# ramp-timebase.net
KiCad netlist of a schematic drawn in EAGLE
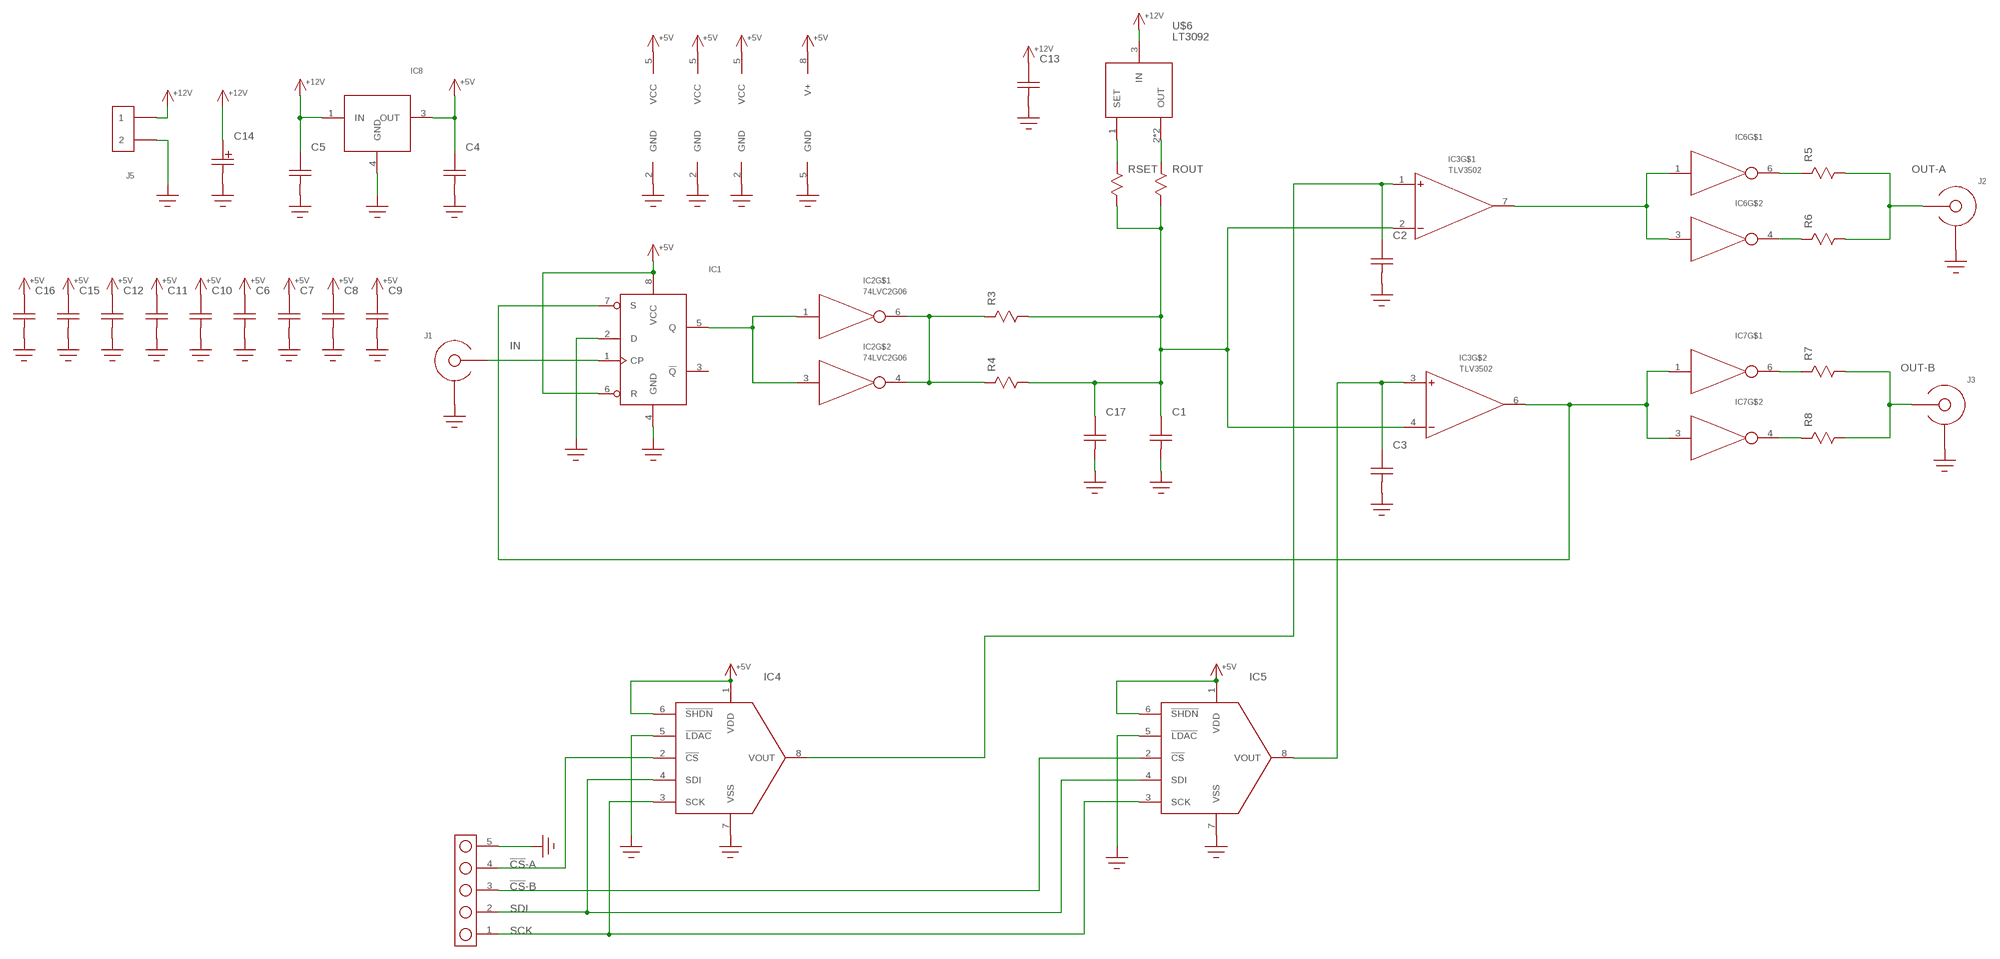
[diagram p0: schematic, sheet 1]

(export (version "E")
  (design (tool "Eeschema 10.0.6"))
  (components
    (comp (ref "C1")
      (value "C0603")
      (footprint "eagle-import:C0603")
      (libsource (lib "eagle-import") (part "C0603"))
    )
    (comp (ref "C2")
      (value "C0603")
      (footprint "eagle-import:C0603")
      (libsource (lib "eagle-import") (part "C0603"))
    )
    (comp (ref "C3")
      (value "C0603")
      (footprint "eagle-import:C0603")
      (libsource (lib "eagle-import") (part "C0603"))
    )
    (comp (ref "C4")
      (value "C1206")
      (footprint "eagle-import:1206")
      (libsource (lib "eagle-import") (part "C1206"))
    )
    (comp (ref "C5")
      (value "C1206")
      (footprint "eagle-import:1206")
      (libsource (lib "eagle-import") (part "C1206"))
    )
    (comp (ref "C6")
      (value "C0603")
      (footprint "eagle-import:C0603")
      (libsource (lib "eagle-import") (part "C0603"))
    )
    (comp (ref "C7")
      (value "C0603")
      (footprint "eagle-import:C0603")
      (libsource (lib "eagle-import") (part "C0603"))
    )
    (comp (ref "C8")
      (value "C0603")
      (footprint "eagle-import:C0603")
      (libsource (lib "eagle-import") (part "C0603"))
    )
    (comp (ref "C9")
      (value "C0603")
      (footprint "eagle-import:C0603")
      (libsource (lib "eagle-import") (part "C0603"))
    )
    (comp (ref "C10")
      (value "C0603")
      (footprint "eagle-import:C0603")
      (libsource (lib "eagle-import") (part "C0603"))
    )
    (comp (ref "C11")
      (value "C0603")
      (footprint "eagle-import:C0603")
      (libsource (lib "eagle-import") (part "C0603"))
    )
    (comp (ref "C12")
      (value "C0603")
      (footprint "eagle-import:C0603")
      (libsource (lib "eagle-import") (part "C0603"))
    )
    (comp (ref "C13")
      (value "C0603")
      (footprint "eagle-import:C0603")
      (libsource (lib "eagle-import") (part "C0603"))
    )
    (comp (ref "C14")
      (value "C-POLARIZED")
      (footprint "eagle-import:CAP-E61")
      (libsource (lib "eagle-import") (part "C-POLARIZED"))
    )
    (comp (ref "C15")
      (value "C0603")
      (footprint "eagle-import:C0603")
      (libsource (lib "eagle-import") (part "C0603"))
    )
    (comp (ref "C16")
      (value "C0603")
      (footprint "eagle-import:C0603")
      (libsource (lib "eagle-import") (part "C0603"))
    )
    (comp (ref "C17")
      (value "C1206")
      (footprint "eagle-import:1206")
      (libsource (lib "eagle-import") (part "C1206"))
    )
    (comp (ref "IC1")
      (value "74LVC2G74")
      (footprint "eagle-import:SSOP8")
      (libsource (lib "eagle-import") (part "74LVC2G74"))
    )
    (comp (ref "IC2")
      (value "74LVC2G06")
      (footprint "eagle-import:SOT23-6")
      (libsource (lib "eagle-import") (part "74LVC2G04"))
    )
    (comp (ref "IC3")
      (value "TLV3502")
      (footprint "eagle-import:SOIC8")
      (libsource (lib "eagle-import") (part "TLV3502"))
    )
    (comp (ref "IC4")
      (value "MCP48X1")
      (footprint "eagle-import:SOIC8")
      (libsource (lib "eagle-import") (part "MCP48X1"))
    )
    (comp (ref "IC5")
      (value "MCP48X1")
      (footprint "eagle-import:SOIC8")
      (libsource (lib "eagle-import") (part "MCP48X1"))
    )
    (comp (ref "IC6")
      (value "74LVC2G04")
      (footprint "eagle-import:SOT23-6")
      (libsource (lib "eagle-import") (part "74LVC2G04"))
    )
    (comp (ref "IC7")
      (value "74LVC2G04")
      (footprint "eagle-import:SOT23-6")
      (libsource (lib "eagle-import") (part "74LVC2G04"))
    )
    (comp (ref "IC8")
      (value "MC78M00")
      (footprint "eagle-import:DPAK")
      (libsource (lib "eagle-import") (part "MC78M00"))
    )
    (comp (ref "J1")
      (value "SMA-EDGE-LAUNCH4020_TAPER")
      (footprint "eagle-import:SMA_EDGE_LAUNCH_2L_4020_TAPER")
      (libsource (lib "eagle-import") (part "SMA-EDGE-LAUNCH4020_TAPER"))
    )
    (comp (ref "J2")
      (value "SMA-EDGE-LAUNCH4020_TAPER")
      (footprint "eagle-import:SMA_EDGE_LAUNCH_2L_4020_TAPER")
      (libsource (lib "eagle-import") (part "SMA-EDGE-LAUNCH4020_TAPER"))
    )
    (comp (ref "J3")
      (value "SMA-EDGE-LAUNCH4020_TAPER")
      (footprint "eagle-import:SMA_EDGE_LAUNCH_2L_4020_TAPER")
      (libsource (lib "eagle-import") (part "SMA-EDGE-LAUNCH4020_TAPER"))
    )
    (comp (ref "J4")
      (value "HEADER_5PIN")
      (footprint "eagle-import:HEADER_5PIN")
      (libsource (lib "eagle-import") (part "HEADER_5PIN"))
    )
    (comp (ref "J5")
      (value "HEADER_2PINSCREW-TERM")
      (footprint "eagle-import:FCI_20020316_SCREW_TERM_2P")
      (libsource (lib "eagle-import") (part "HEADER_2PINSCREW-TERM"))
    )
    (comp (ref "R3")
      (value "R0805")
      (footprint "eagle-import:R0805")
      (libsource (lib "eagle-import") (part "R0805"))
    )
    (comp (ref "R4")
      (value "R0805")
      (footprint "eagle-import:R0805")
      (libsource (lib "eagle-import") (part "R0805"))
    )
    (comp (ref "R5")
      (value "R1206")
      (footprint "eagle-import:R1206")
      (libsource (lib "eagle-import") (part "R1206"))
    )
    (comp (ref "R6")
      (value "R1206")
      (footprint "eagle-import:R1206")
      (libsource (lib "eagle-import") (part "R1206"))
    )
    (comp (ref "R7")
      (value "R1206")
      (footprint "eagle-import:R1206")
      (libsource (lib "eagle-import") (part "R1206"))
    )
    (comp (ref "R8")
      (value "R1206")
      (footprint "eagle-import:R1206")
      (libsource (lib "eagle-import") (part "R1206"))
    )
    (comp (ref "ROUT")
      (value "R0805")
      (footprint "eagle-import:R0805")
      (libsource (lib "eagle-import") (part "R0805"))
    )
    (comp (ref "RSET")
      (value "R0805")
      (footprint "eagle-import:R0805")
      (libsource (lib "eagle-import") (part "R0805"))
    )
    (comp (ref "U$6")
      (value "LT3092")
      (footprint "eagle-import:SOT-223")
      (libsource (lib "eagle-import") (part "LT3092"))
    )
  )
  (nets
    (net (code "1") (name "+5V") (class "Default")
      (node (ref "C10") (pin "P$2") (pinfunction "P$2_P$2") (pintype "bidirectional"))
      (node (ref "C11") (pin "P$2") (pinfunction "P$2_P$2") (pintype "bidirectional"))
      (node (ref "C12") (pin "P$2") (pinfunction "P$2_P$2") (pintype "bidirectional"))
      (node (ref "C15") (pin "P$2") (pinfunction "P$2_P$2") (pintype "bidirectional"))
      (node (ref "C16") (pin "P$2") (pinfunction "P$2_P$2") (pintype "bidirectional"))
      (node (ref "C4") (pin "P$2") (pinfunction "P$2_P$2") (pintype "bidirectional"))
      (node (ref "C6") (pin "P$2") (pinfunction "P$2_P$2") (pintype "bidirectional"))
      (node (ref "C7") (pin "P$2") (pinfunction "P$2_P$2") (pintype "bidirectional"))
      (node (ref "C8") (pin "P$2") (pinfunction "P$2_P$2") (pintype "bidirectional"))
      (node (ref "C9") (pin "P$2") (pinfunction "P$2_P$2") (pintype "bidirectional"))
      (node (ref "IC1") (pin "6") (pinfunction "R_6") (pintype "bidirectional"))
      (node (ref "IC1") (pin "8") (pinfunction "VCC_8") (pintype "bidirectional"))
      (node (ref "IC2") (pin "5") (pinfunction "VCC_5") (pintype "bidirectional"))
      (node (ref "IC3") (pin "8") (pinfunction "V+_8") (pintype "bidirectional"))
      (node (ref "IC4") (pin "1") (pinfunction "VDD_1") (pintype "bidirectional"))
      (node (ref "IC4") (pin "6") (pinfunction "~{SHDN}_6") (pintype "bidirectional"))
      (node (ref "IC5") (pin "1") (pinfunction "VDD_1") (pintype "bidirectional"))
      (node (ref "IC5") (pin "6") (pinfunction "~{SHDN}_6") (pintype "bidirectional"))
      (node (ref "IC6") (pin "5") (pinfunction "VCC_5") (pintype "bidirectional"))
      (node (ref "IC7") (pin "5") (pinfunction "VCC_5") (pintype "bidirectional"))
      (node (ref "IC8") (pin "3") (pinfunction "OUT_3") (pintype "bidirectional"))
    )
    (net (code "2") (name "+12V") (class "Default")
      (node (ref "C13") (pin "P$2") (pinfunction "P$2_P$2") (pintype "bidirectional"))
      (node (ref "C14") (pin "+") (pinfunction "+_+") (pintype "bidirectional"))
      (node (ref "C5") (pin "P$2") (pinfunction "P$2_P$2") (pintype "bidirectional"))
      (node (ref "IC8") (pin "1") (pinfunction "IN_1") (pintype "bidirectional"))
      (node (ref "J5") (pin "P$1") (pinfunction "1_P$1") (pintype "bidirectional"))
      (node (ref "U$6") (pin "3") (pinfunction "IN_3") (pintype "bidirectional"))
    )
    (net (code "3") (name "/IN") (class "Default")
      (node (ref "IC1") (pin "1") (pinfunction "CP_1") (pintype "bidirectional"))
      (node (ref "J1") (pin "CENTER@1") (pinfunction "CENTER_CENTER@1") (pintype "bidirectional"))
    )
    (net (code "4") (name "/OUT-A") (class "Default")
      (node (ref "J2") (pin "CENTER@1") (pinfunction "CENTER_CENTER@1") (pintype "bidirectional"))
      (node (ref "R5") (pin "P$2") (pinfunction "P$4_P$2") (pintype "bidirectional"))
      (node (ref "R6") (pin "P$2") (pinfunction "P$4_P$2") (pintype "bidirectional"))
    )
    (net (code "5") (name "/OUT-B") (class "Default")
      (node (ref "J3") (pin "CENTER@1") (pinfunction "CENTER_CENTER@1") (pintype "bidirectional"))
      (node (ref "R7") (pin "P$2") (pinfunction "P$4_P$2") (pintype "bidirectional"))
      (node (ref "R8") (pin "P$2") (pinfunction "P$4_P$2") (pintype "bidirectional"))
    )
    (net (code "6") (name "/SCK") (class "Default")
      (node (ref "IC4") (pin "3") (pinfunction "SCK_3") (pintype "bidirectional"))
      (node (ref "IC5") (pin "3") (pinfunction "SCK_3") (pintype "bidirectional"))
      (node (ref "J4") (pin "1") (pinfunction "1_1") (pintype "bidirectional"))
    )
    (net (code "7") (name "/SDI") (class "Default")
      (node (ref "IC4") (pin "4") (pinfunction "SDI_4") (pintype "bidirectional"))
      (node (ref "IC5") (pin "4") (pinfunction "SDI_4") (pintype "bidirectional"))
      (node (ref "J4") (pin "2") (pinfunction "2_2") (pintype "bidirectional"))
    )
    (net (code "8") (name "/~{CS}-A") (class "Default")
      (node (ref "IC4") (pin "2") (pinfunction "~{CS}_2") (pintype "bidirectional"))
      (node (ref "J4") (pin "4") (pinfunction "4_4") (pintype "bidirectional"))
    )
    (net (code "9") (name "/~{CS}-B") (class "Default")
      (node (ref "IC5") (pin "2") (pinfunction "~{CS}_2") (pintype "bidirectional"))
      (node (ref "J4") (pin "3") (pinfunction "3_3") (pintype "bidirectional"))
    )
    (net (code "10") (name "GND") (class "Default")
      (node (ref "C1") (pin "P$1") (pinfunction "P$1_P$1") (pintype "bidirectional"))
      (node (ref "C10") (pin "P$1") (pinfunction "P$1_P$1") (pintype "bidirectional"))
      (node (ref "C11") (pin "P$1") (pinfunction "P$1_P$1") (pintype "bidirectional"))
      (node (ref "C12") (pin "P$1") (pinfunction "P$1_P$1") (pintype "bidirectional"))
      (node (ref "C13") (pin "P$1") (pinfunction "P$1_P$1") (pintype "bidirectional"))
      (node (ref "C14") (pin "-") (pinfunction "-_-") (pintype "bidirectional"))
      (node (ref "C15") (pin "P$1") (pinfunction "P$1_P$1") (pintype "bidirectional"))
      (node (ref "C16") (pin "P$1") (pinfunction "P$1_P$1") (pintype "bidirectional"))
      (node (ref "C17") (pin "P$1") (pinfunction "P$1_P$1") (pintype "bidirectional"))
      (node (ref "C2") (pin "P$1") (pinfunction "P$1_P$1") (pintype "bidirectional"))
      (node (ref "C3") (pin "P$1") (pinfunction "P$1_P$1") (pintype "bidirectional"))
      (node (ref "C4") (pin "P$1") (pinfunction "P$1_P$1") (pintype "bidirectional"))
      (node (ref "C5") (pin "P$1") (pinfunction "P$1_P$1") (pintype "bidirectional"))
      (node (ref "C6") (pin "P$1") (pinfunction "P$1_P$1") (pintype "bidirectional"))
      (node (ref "C7") (pin "P$1") (pinfunction "P$1_P$1") (pintype "bidirectional"))
      (node (ref "C8") (pin "P$1") (pinfunction "P$1_P$1") (pintype "bidirectional"))
      (node (ref "C9") (pin "P$1") (pinfunction "P$1_P$1") (pintype "bidirectional"))
      (node (ref "IC1") (pin "2") (pinfunction "D_2") (pintype "bidirectional"))
      (node (ref "IC1") (pin "4") (pinfunction "GND_4") (pintype "bidirectional"))
      (node (ref "IC2") (pin "2") (pinfunction "GND_2") (pintype "bidirectional"))
      (node (ref "IC3") (pin "5") (pinfunction "GND_5") (pintype "bidirectional"))
      (node (ref "IC4") (pin "5") (pinfunction "~{LDAC}_5") (pintype "bidirectional"))
      (node (ref "IC4") (pin "7") (pinfunction "VSS_7") (pintype "bidirectional"))
      (node (ref "IC5") (pin "5") (pinfunction "~{LDAC}_5") (pintype "bidirectional"))
      (node (ref "IC5") (pin "7") (pinfunction "VSS_7") (pintype "bidirectional"))
      (node (ref "IC6") (pin "2") (pinfunction "GND_2") (pintype "bidirectional"))
      (node (ref "IC7") (pin "2") (pinfunction "GND_2") (pintype "bidirectional"))
      (node (ref "IC8") (pin "4") (pinfunction "GND_4") (pintype "bidirectional"))
      (node (ref "J1") (pin "BOTTOM_GND") (pinfunction "SHIELD_BOTTOM_GND") (pintype "bidirectional"))
      (node (ref "J1") (pin "GND@1") (pinfunction "SHIELD_GND@1") (pintype "bidirectional"))
      (node (ref "J1") (pin "GND@14") (pinfunction "SHIELD_GND@14") (pintype "bidirectional"))
      (node (ref "J1") (pin "GND@15") (pinfunction "SHIELD_GND@15") (pintype "bidirectional"))
      (node (ref "J1") (pin "GND@16") (pinfunction "SHIELD_GND@16") (pintype "bidirectional"))
      (node (ref "J1") (pin "GND@17") (pinfunction "SHIELD_GND@17") (pintype "bidirectional"))
      (node (ref "J1") (pin "GND@2") (pinfunction "SHIELD_GND@2") (pintype "bidirectional"))
      (node (ref "J1") (pin "GND@3") (pinfunction "SHIELD_GND@3") (pintype "bidirectional"))
      (node (ref "J1") (pin "GND@4") (pinfunction "SHIELD_GND@4") (pintype "bidirectional"))
      (node (ref "J1") (pin "GND@5") (pinfunction "SHIELD_GND@5") (pintype "bidirectional"))
      (node (ref "J1") (pin "GND@6") (pinfunction "SHIELD_GND@6") (pintype "bidirectional"))
      (node (ref "J1") (pin "GND@7") (pinfunction "SHIELD_GND@7") (pintype "bidirectional"))
      (node (ref "J1") (pin "GND@8") (pinfunction "SHIELD_GND@8") (pintype "bidirectional"))
      (node (ref "J1") (pin "GND_PAD1") (pinfunction "SHIELD_GND_PAD1") (pintype "bidirectional"))
      (node (ref "J1") (pin "GND_PAD2") (pinfunction "SHIELD_GND_PAD2") (pintype "bidirectional"))
      (node (ref "J1") (pin "P$1") (pinfunction "SHIELD_P$1") (pintype "bidirectional"))
      (node (ref "J1") (pin "P$2") (pinfunction "SHIELD_P$2") (pintype "bidirectional"))
      (node (ref "J2") (pin "BOTTOM_GND") (pinfunction "SHIELD_BOTTOM_GND") (pintype "bidirectional"))
      (node (ref "J2") (pin "GND@1") (pinfunction "SHIELD_GND@1") (pintype "bidirectional"))
      (node (ref "J2") (pin "GND@14") (pinfunction "SHIELD_GND@14") (pintype "bidirectional"))
      (node (ref "J2") (pin "GND@15") (pinfunction "SHIELD_GND@15") (pintype "bidirectional"))
      (node (ref "J2") (pin "GND@16") (pinfunction "SHIELD_GND@16") (pintype "bidirectional"))
      (node (ref "J2") (pin "GND@17") (pinfunction "SHIELD_GND@17") (pintype "bidirectional"))
      (node (ref "J2") (pin "GND@2") (pinfunction "SHIELD_GND@2") (pintype "bidirectional"))
      (node (ref "J2") (pin "GND@3") (pinfunction "SHIELD_GND@3") (pintype "bidirectional"))
      (node (ref "J2") (pin "GND@4") (pinfunction "SHIELD_GND@4") (pintype "bidirectional"))
      (node (ref "J2") (pin "GND@5") (pinfunction "SHIELD_GND@5") (pintype "bidirectional"))
      (node (ref "J2") (pin "GND@6") (pinfunction "SHIELD_GND@6") (pintype "bidirectional"))
      (node (ref "J2") (pin "GND@7") (pinfunction "SHIELD_GND@7") (pintype "bidirectional"))
      (node (ref "J2") (pin "GND@8") (pinfunction "SHIELD_GND@8") (pintype "bidirectional"))
      (node (ref "J2") (pin "GND_PAD1") (pinfunction "SHIELD_GND_PAD1") (pintype "bidirectional"))
      (node (ref "J2") (pin "GND_PAD2") (pinfunction "SHIELD_GND_PAD2") (pintype "bidirectional"))
      (node (ref "J2") (pin "P$1") (pinfunction "SHIELD_P$1") (pintype "bidirectional"))
      (node (ref "J2") (pin "P$2") (pinfunction "SHIELD_P$2") (pintype "bidirectional"))
      (node (ref "J3") (pin "BOTTOM_GND") (pinfunction "SHIELD_BOTTOM_GND") (pintype "bidirectional"))
      (node (ref "J3") (pin "GND@1") (pinfunction "SHIELD_GND@1") (pintype "bidirectional"))
      (node (ref "J3") (pin "GND@14") (pinfunction "SHIELD_GND@14") (pintype "bidirectional"))
      (node (ref "J3") (pin "GND@15") (pinfunction "SHIELD_GND@15") (pintype "bidirectional"))
      (node (ref "J3") (pin "GND@16") (pinfunction "SHIELD_GND@16") (pintype "bidirectional"))
      (node (ref "J3") (pin "GND@17") (pinfunction "SHIELD_GND@17") (pintype "bidirectional"))
      (node (ref "J3") (pin "GND@2") (pinfunction "SHIELD_GND@2") (pintype "bidirectional"))
      (node (ref "J3") (pin "GND@3") (pinfunction "SHIELD_GND@3") (pintype "bidirectional"))
      (node (ref "J3") (pin "GND@4") (pinfunction "SHIELD_GND@4") (pintype "bidirectional"))
      (node (ref "J3") (pin "GND@5") (pinfunction "SHIELD_GND@5") (pintype "bidirectional"))
      (node (ref "J3") (pin "GND@6") (pinfunction "SHIELD_GND@6") (pintype "bidirectional"))
      (node (ref "J3") (pin "GND@7") (pinfunction "SHIELD_GND@7") (pintype "bidirectional"))
      (node (ref "J3") (pin "GND@8") (pinfunction "SHIELD_GND@8") (pintype "bidirectional"))
      (node (ref "J3") (pin "GND_PAD1") (pinfunction "SHIELD_GND_PAD1") (pintype "bidirectional"))
      (node (ref "J3") (pin "GND_PAD2") (pinfunction "SHIELD_GND_PAD2") (pintype "bidirectional"))
      (node (ref "J3") (pin "P$1") (pinfunction "SHIELD_P$1") (pintype "bidirectional"))
      (node (ref "J3") (pin "P$2") (pinfunction "SHIELD_P$2") (pintype "bidirectional"))
      (node (ref "J4") (pin "5") (pinfunction "5_5") (pintype "bidirectional"))
      (node (ref "J5") (pin "P$2") (pinfunction "2_P$2") (pintype "bidirectional"))
    )
    (net (code "11") (name "Net-(IC1-Q)") (class "Default")
      (node (ref "IC1") (pin "5") (pinfunction "Q_5") (pintype "bidirectional"))
      (node (ref "IC2") (pin "1") (pinfunction "IN_1") (pintype "bidirectional"))
      (node (ref "IC2") (pin "3") (pinfunction "IN_3") (pintype "bidirectional"))
    )
    (net (code "12") (name "Net-(IC1-S)") (class "Default")
      (node (ref "IC1") (pin "7") (pinfunction "S_7") (pintype "bidirectional"))
      (node (ref "IC3") (pin "6") (pinfunction "OUT_6") (pintype "bidirectional"))
      (node (ref "IC7") (pin "1") (pinfunction "IN_1") (pintype "bidirectional"))
      (node (ref "IC7") (pin "3") (pinfunction "IN_3") (pintype "bidirectional"))
    )
    (net (code "13") (name "Net-(IC2A-OUT)") (class "Default")
      (node (ref "IC2") (pin "4") (pinfunction "OUT_4") (pintype "bidirectional"))
      (node (ref "IC2") (pin "6") (pinfunction "OUT_6") (pintype "bidirectional"))
      (node (ref "R3") (pin "P$1") (pinfunction "P$3_P$1") (pintype "bidirectional"))
      (node (ref "R4") (pin "P$1") (pinfunction "P$3_P$1") (pintype "bidirectional"))
    )
    (net (code "14") (name "Net-(IC3A-+)") (class "Default")
      (node (ref "C2") (pin "P$2") (pinfunction "P$2_P$2") (pintype "bidirectional"))
      (node (ref "IC3") (pin "1") (pinfunction "+_1") (pintype "bidirectional"))
      (node (ref "IC4") (pin "8") (pinfunction "VOUT_8") (pintype "bidirectional"))
    )
    (net (code "15") (name "Net-(IC3A--)") (class "Default")
      (node (ref "C1") (pin "P$2") (pinfunction "P$2_P$2") (pintype "bidirectional"))
      (node (ref "C17") (pin "P$2") (pinfunction "P$2_P$2") (pintype "bidirectional"))
      (node (ref "IC3") (pin "2") (pinfunction "-_2") (pintype "bidirectional"))
      (node (ref "IC3") (pin "4") (pinfunction "-_4") (pintype "bidirectional"))
      (node (ref "R3") (pin "P$2") (pinfunction "P$4_P$2") (pintype "bidirectional"))
      (node (ref "R4") (pin "P$2") (pinfunction "P$4_P$2") (pintype "bidirectional"))
      (node (ref "ROUT") (pin "P$2") (pinfunction "P$4_P$2") (pintype "bidirectional"))
      (node (ref "RSET") (pin "P$2") (pinfunction "P$4_P$2") (pintype "bidirectional"))
    )
    (net (code "16") (name "Net-(IC3A-OUT)") (class "Default")
      (node (ref "IC3") (pin "7") (pinfunction "OUT_7") (pintype "bidirectional"))
      (node (ref "IC6") (pin "1") (pinfunction "IN_1") (pintype "bidirectional"))
      (node (ref "IC6") (pin "3") (pinfunction "IN_3") (pintype "bidirectional"))
    )
    (net (code "17") (name "Net-(IC3B-+)") (class "Default")
      (node (ref "C3") (pin "P$2") (pinfunction "P$2_P$2") (pintype "bidirectional"))
      (node (ref "IC3") (pin "3") (pinfunction "+_3") (pintype "bidirectional"))
      (node (ref "IC5") (pin "8") (pinfunction "VOUT_8") (pintype "bidirectional"))
    )
    (net (code "18") (name "Net-(IC6A-OUT)") (class "Default")
      (node (ref "IC6") (pin "6") (pinfunction "OUT_6") (pintype "bidirectional"))
      (node (ref "R5") (pin "P$1") (pinfunction "P$3_P$1") (pintype "bidirectional"))
    )
    (net (code "19") (name "Net-(IC6B-OUT)") (class "Default")
      (node (ref "IC6") (pin "4") (pinfunction "OUT_4") (pintype "bidirectional"))
      (node (ref "R6") (pin "P$1") (pinfunction "P$3_P$1") (pintype "bidirectional"))
    )
    (net (code "20") (name "Net-(IC7A-OUT)") (class "Default")
      (node (ref "IC7") (pin "6") (pinfunction "OUT_6") (pintype "bidirectional"))
      (node (ref "R7") (pin "P$1") (pinfunction "P$3_P$1") (pintype "bidirectional"))
    )
    (net (code "21") (name "Net-(IC7B-OUT)") (class "Default")
      (node (ref "IC7") (pin "4") (pinfunction "OUT_4") (pintype "bidirectional"))
      (node (ref "R8") (pin "P$1") (pinfunction "P$3_P$1") (pintype "bidirectional"))
    )
    (net (code "22") (name "Net-(ROUT-P$3)") (class "Default")
      (node (ref "ROUT") (pin "P$1") (pinfunction "P$3_P$1") (pintype "bidirectional"))
      (node (ref "U$6") (pin "2") (pinfunction "OUT_2") (pintype "bidirectional"))
      (node (ref "U$6") (pin "4") (pinfunction "OUT_4") (pintype "bidirectional"))
    )
    (net (code "23") (name "Net-(RSET-P$3)") (class "Default")
      (node (ref "RSET") (pin "P$1") (pinfunction "P$3_P$1") (pintype "bidirectional"))
      (node (ref "U$6") (pin "1") (pinfunction "SET_1") (pintype "bidirectional"))
    )
    (net (code "24") (name "unconnected-(IC1-~{Q}-Pad3)") (class "Default")
      (node (ref "IC1") (pin "3") (pinfunction "~{Q}_3") (pintype "bidirectional"))
    )
  )
)
